# ETHERBEAR.net
KiCad netlist of a schematic drawn in EAGLE
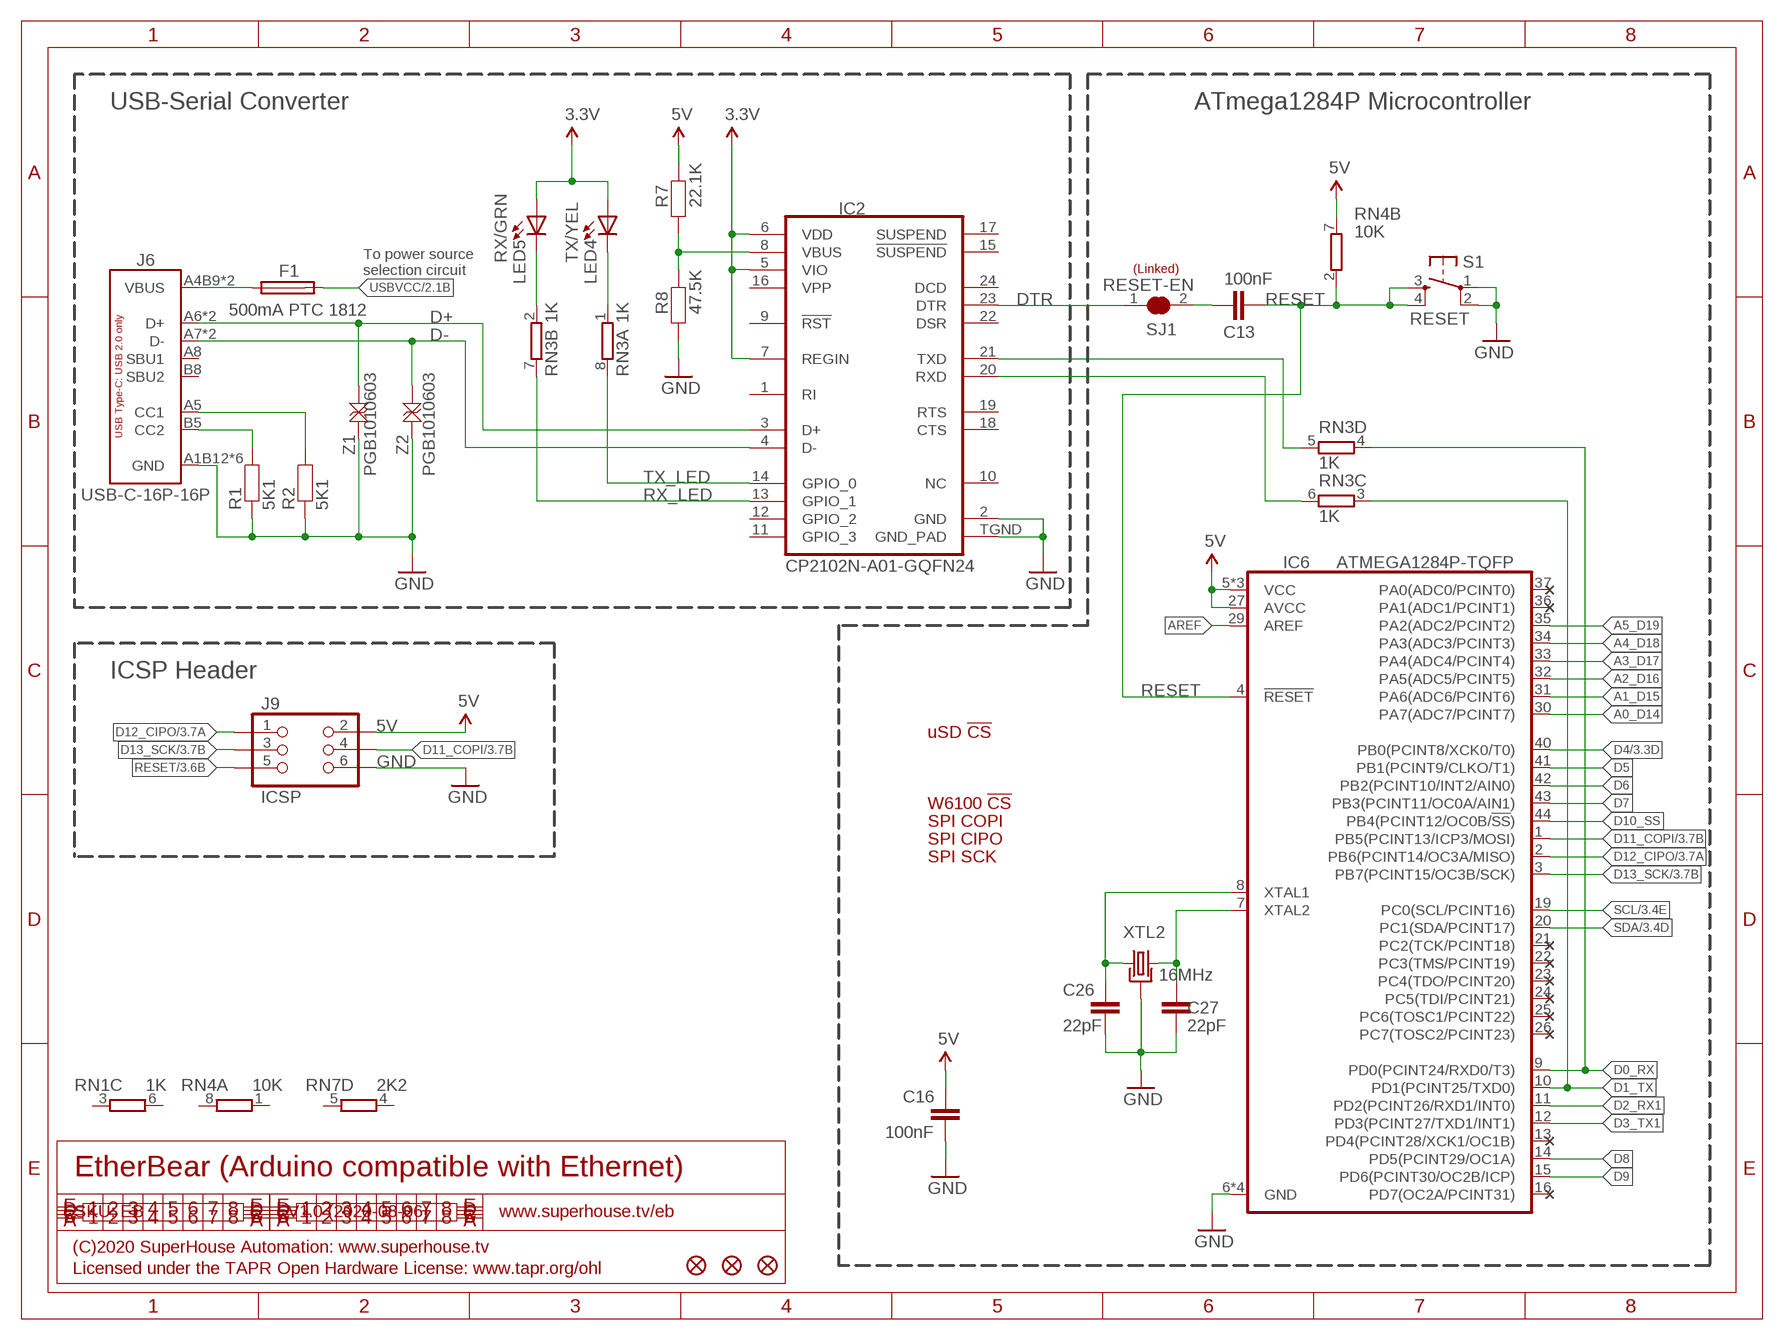
[diagram p0: schematic, sheet 1]
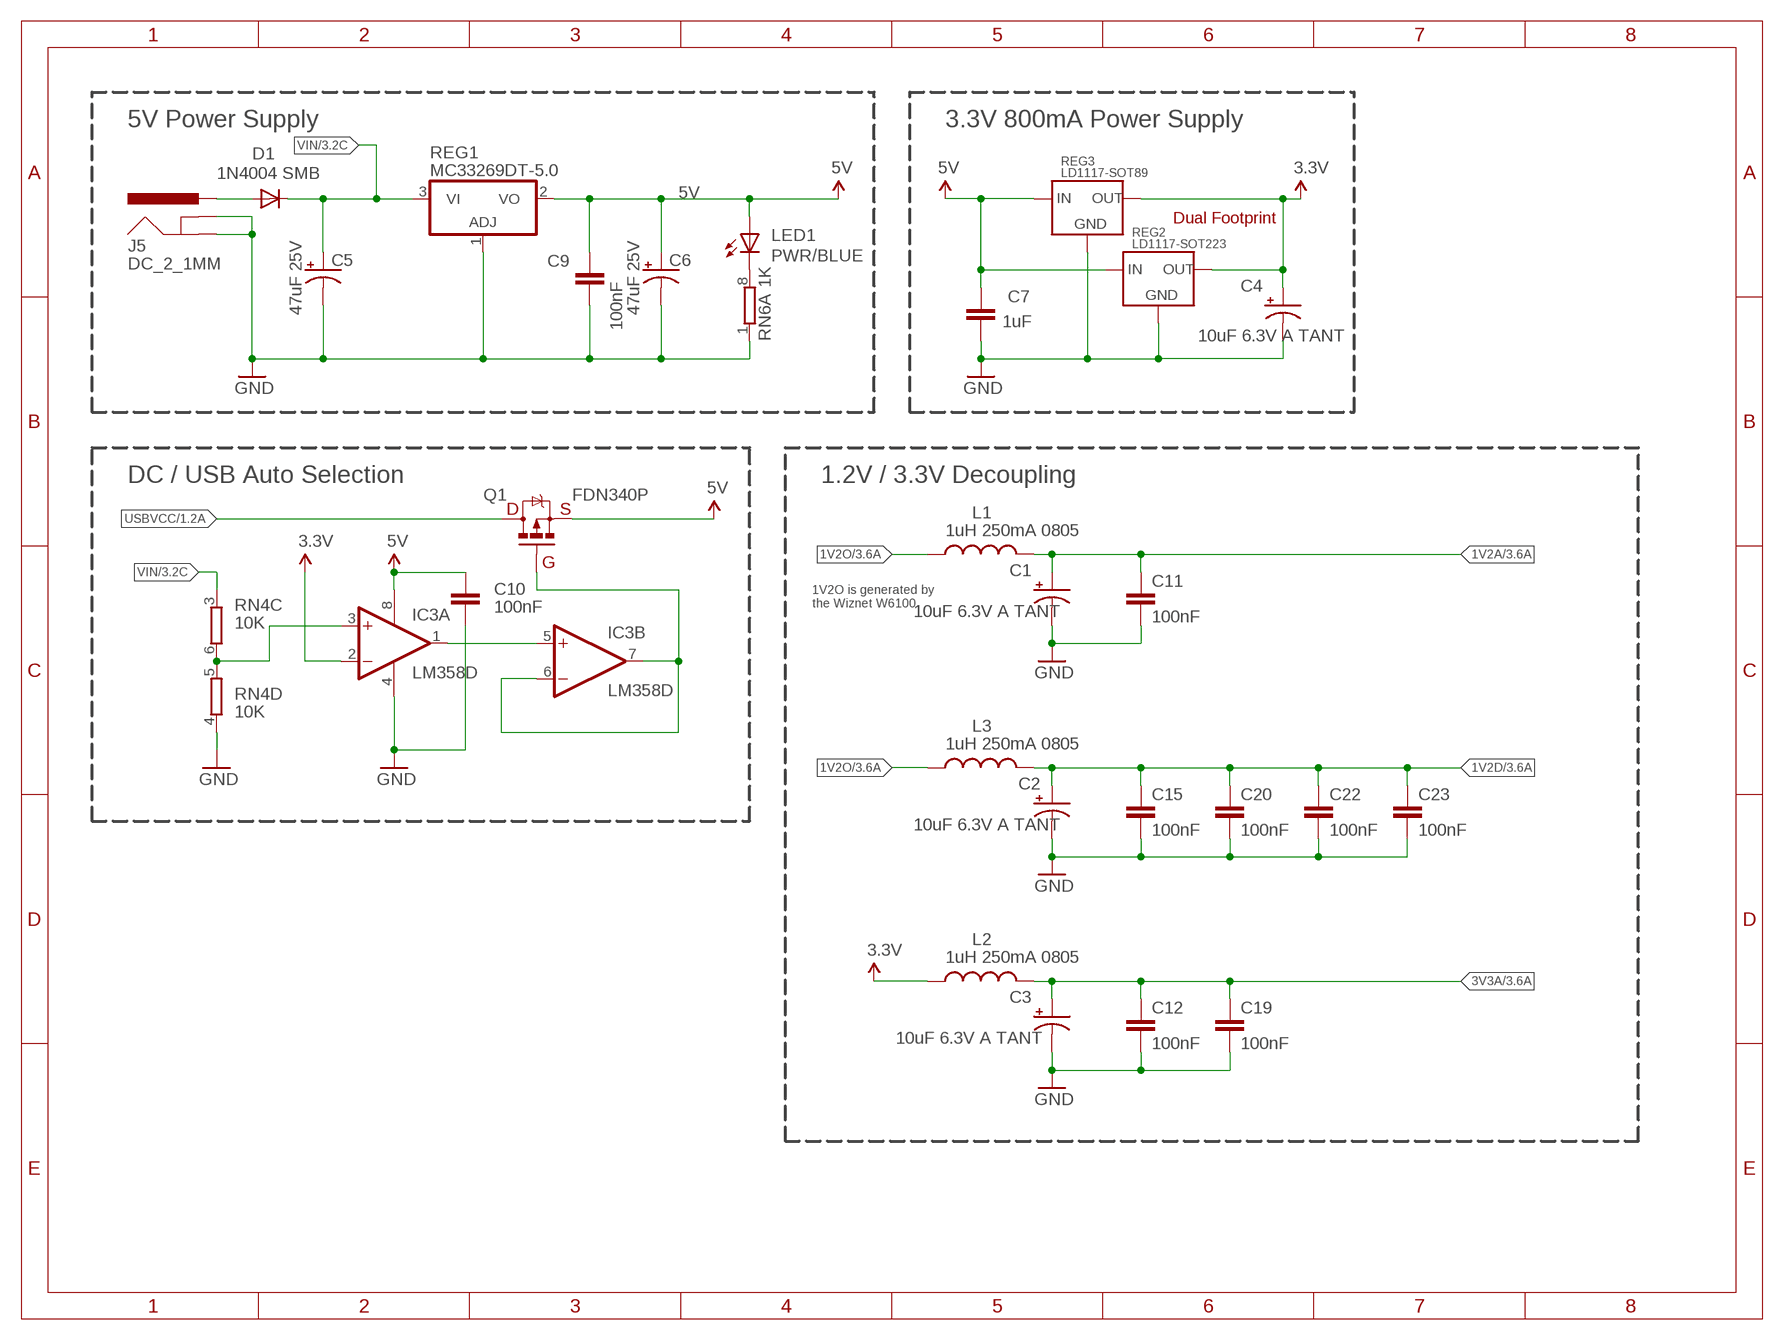
[diagram p1: schematic, sheet 2]
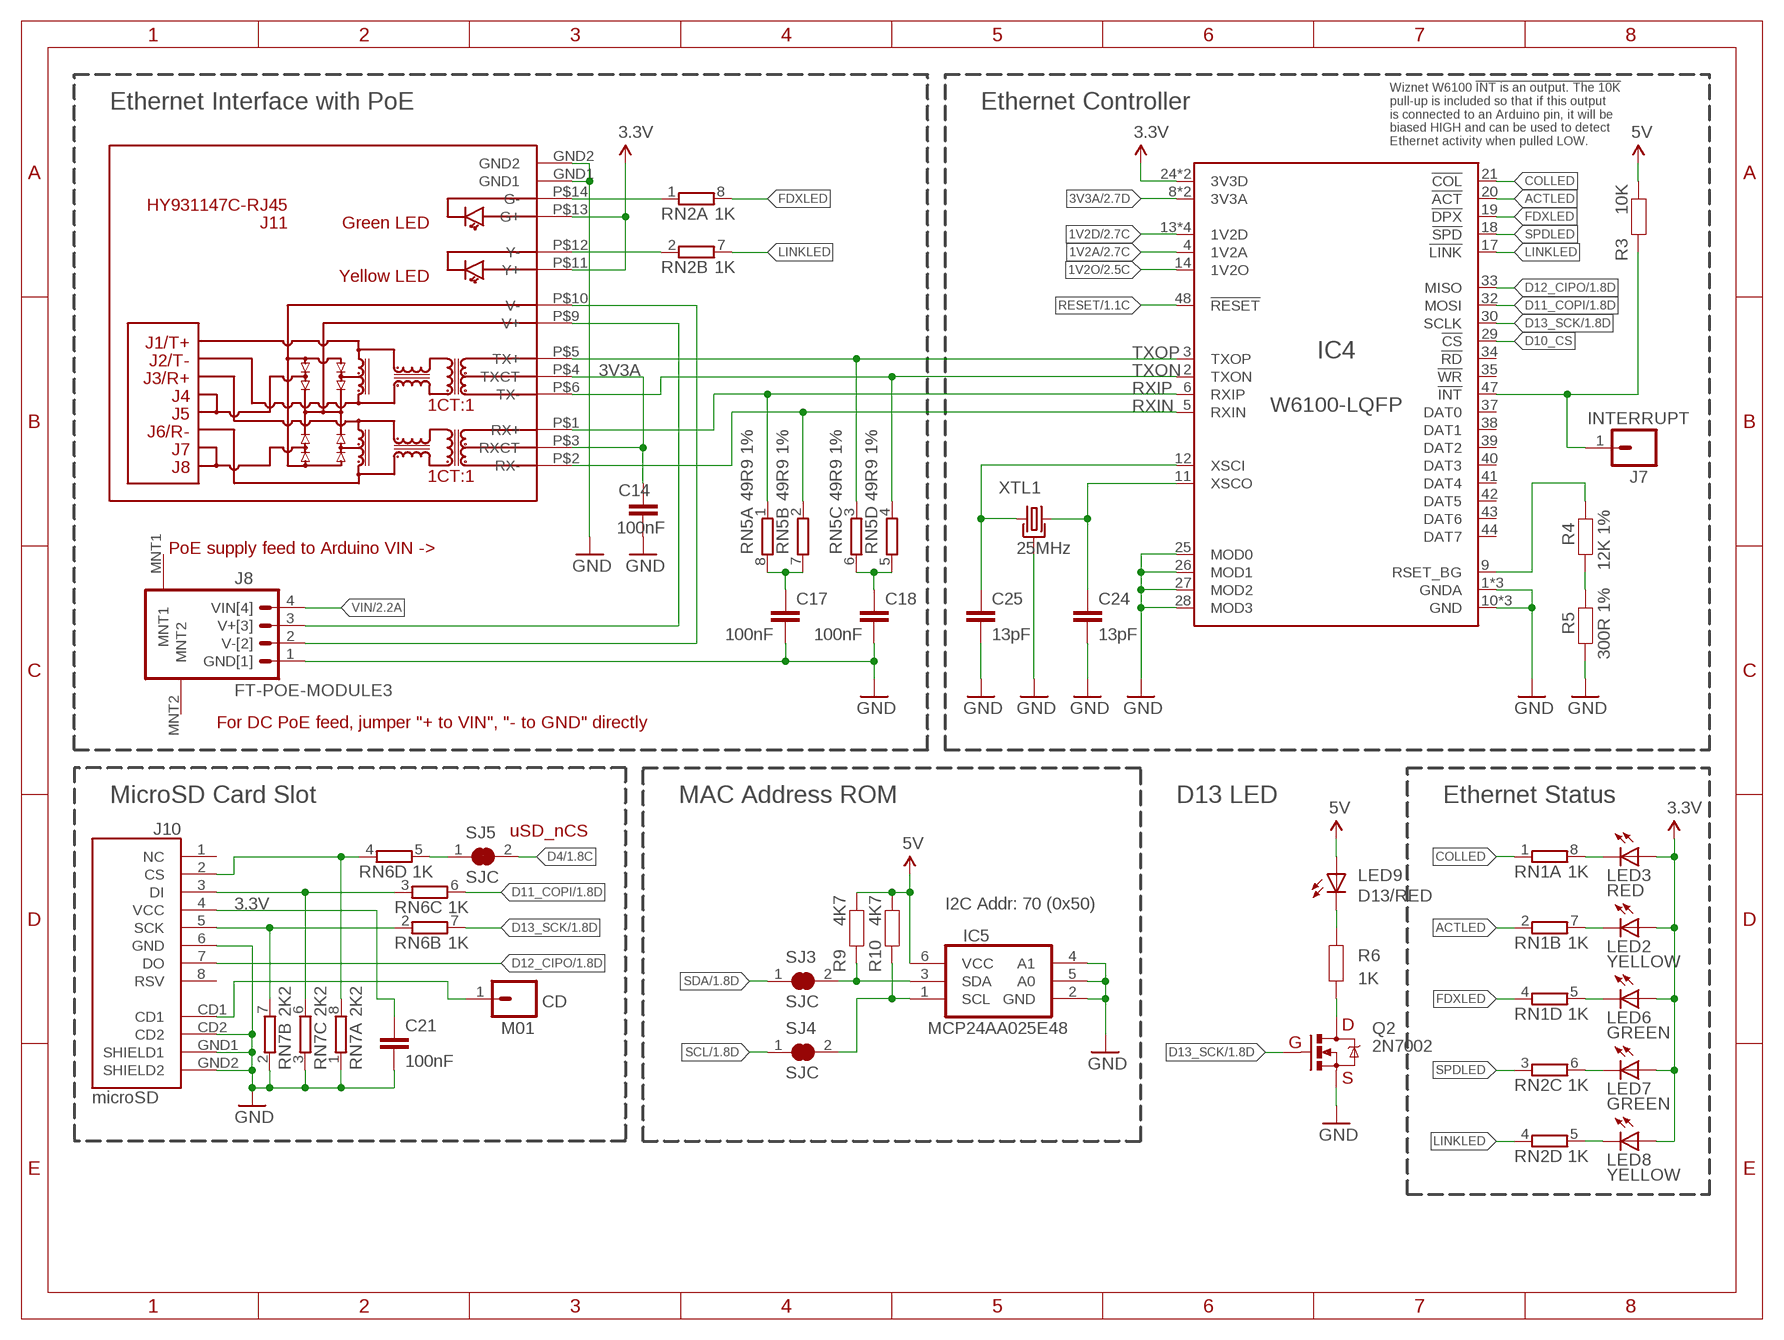
[diagram p2: schematic, sheet 3]
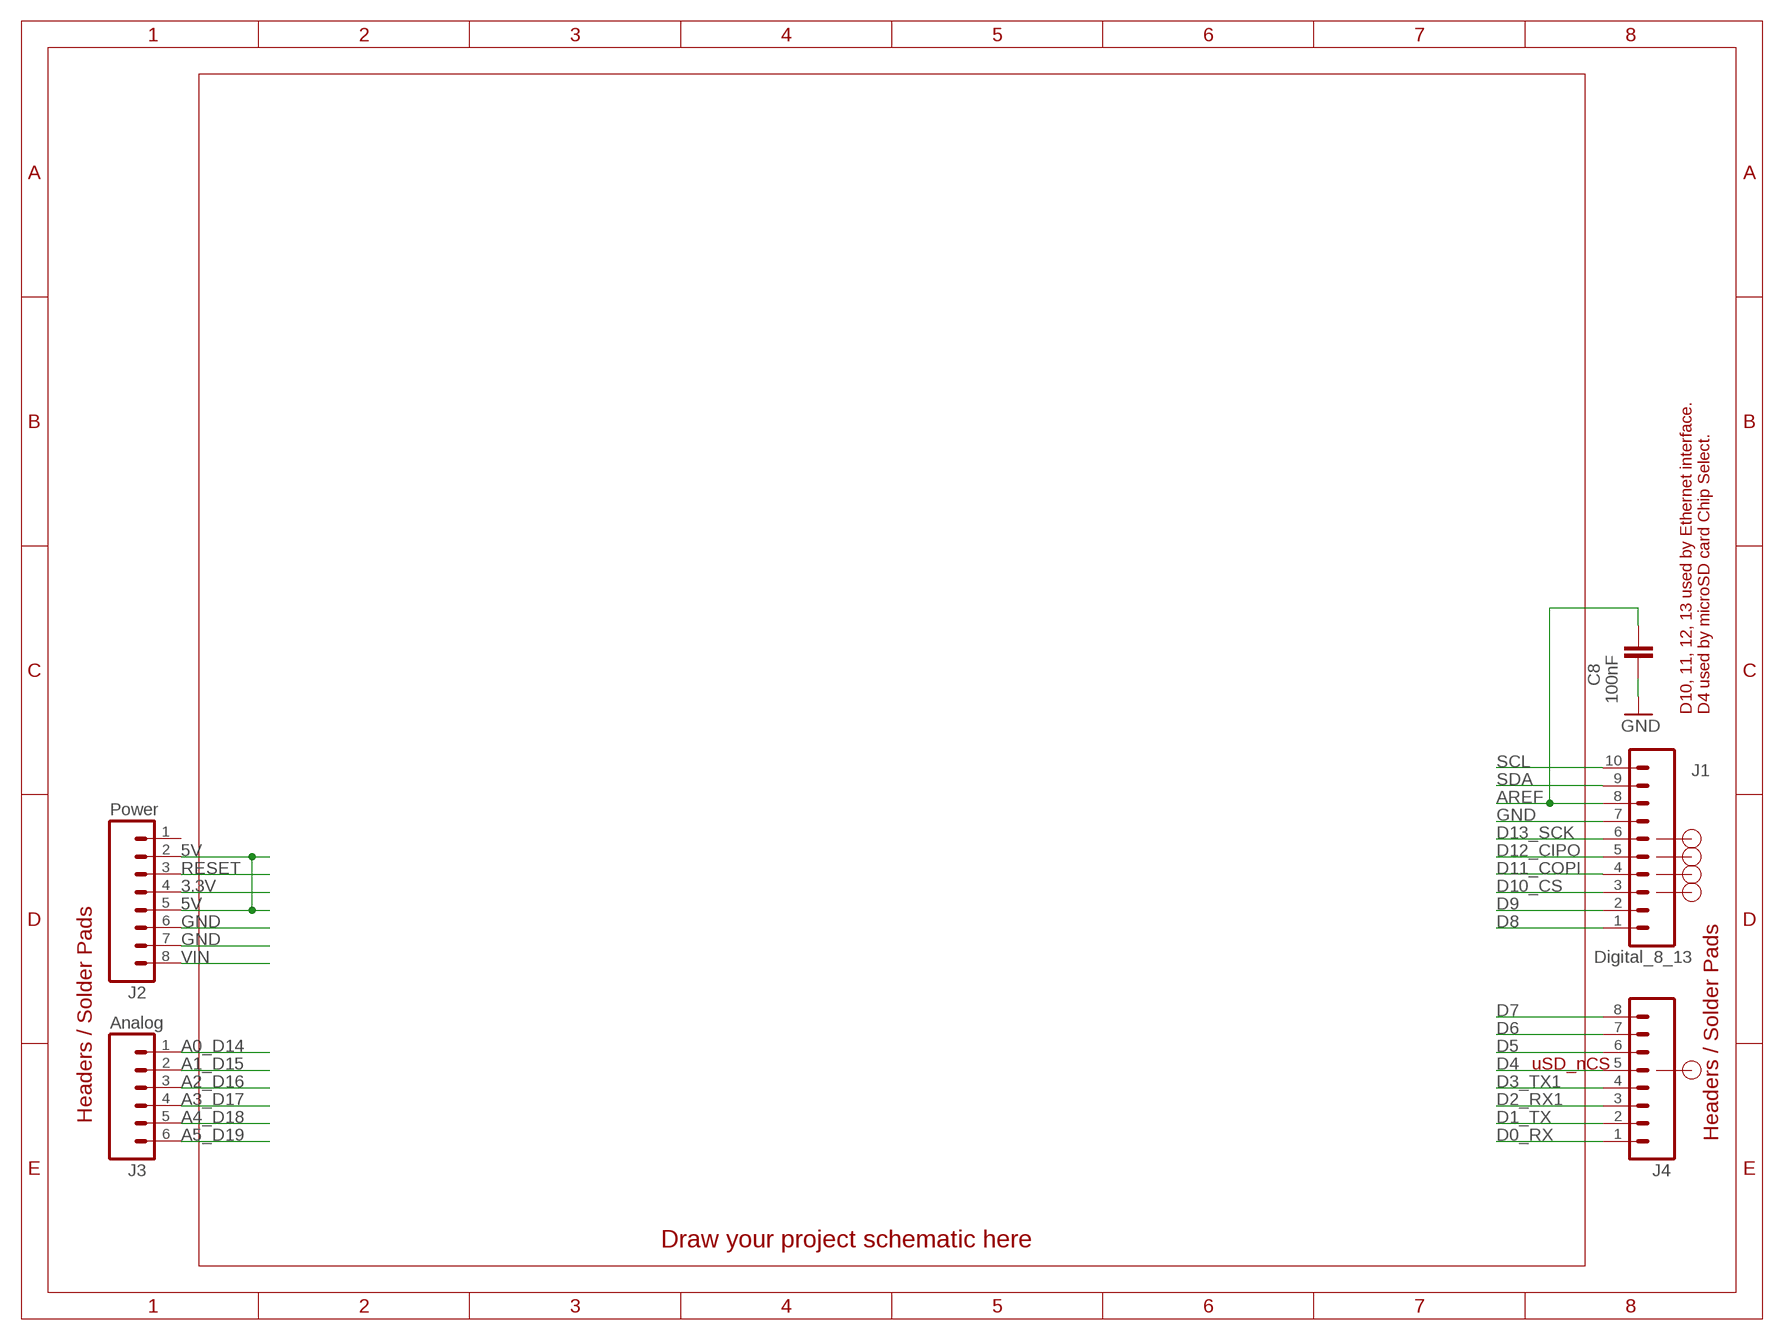
[diagram p3: schematic, sheet 4]

(export (version "E")
  (design (tool "Eeschema 10.0.6"))
  (components
    (comp (ref "C1")
      (value "10uF 6.3V A TANT")
      (footprint "eagle-import:EIA3216")
      (libsource (lib "eagle-import") (part "CAP_POL1206"))
    )
    (comp (ref "C2")
      (value "10uF 6.3V A TANT")
      (footprint "eagle-import:EIA3216")
      (libsource (lib "eagle-import") (part "CAP_POL1206"))
    )
    (comp (ref "C3")
      (value "10uF 6.3V A TANT")
      (footprint "eagle-import:EIA3216")
      (libsource (lib "eagle-import") (part "CAP_POL1206"))
    )
    (comp (ref "C4")
      (value "10uF 6.3V A TANT")
      (footprint "eagle-import:EIA3216")
      (libsource (lib "eagle-import") (part "CAP_POL1206"))
    )
    (comp (ref "C5")
      (value "47uF 25V")
      (footprint "eagle-import:PANASONIC_D")
      (libsource (lib "eagle-import") (part "CAP_POLD"))
    )
    (comp (ref "C6")
      (value "47uF 25V")
      (footprint "eagle-import:PANASONIC_D")
      (libsource (lib "eagle-import") (part "CAP_POLD"))
    )
    (comp (ref "C7")
      (value "1uF")
      (footprint "eagle-import:C0603")
      (libsource (lib "eagle-import") (part "CAP0603"))
    )
    (comp (ref "C9")
      (value "100nF")
      (footprint "eagle-import:C0603")
      (libsource (lib "eagle-import") (part "CAP0603"))
    )
    (comp (ref "C10")
      (value "100nF")
      (footprint "eagle-import:C0603")
      (libsource (lib "eagle-import") (part "CAP0603"))
    )
    (comp (ref "C11")
      (value "100nF")
      (footprint "eagle-import:C0603")
      (libsource (lib "eagle-import") (part "CAP0603"))
    )
    (comp (ref "C12")
      (value "100nF")
      (footprint "eagle-import:C0603")
      (libsource (lib "eagle-import") (part "CAP0603"))
    )
    (comp (ref "C15")
      (value "100nF")
      (footprint "eagle-import:C0603")
      (libsource (lib "eagle-import") (part "CAP0603"))
    )
    (comp (ref "C19")
      (value "100nF")
      (footprint "eagle-import:C0603")
      (libsource (lib "eagle-import") (part "CAP0603"))
    )
    (comp (ref "C20")
      (value "100nF")
      (footprint "eagle-import:C0603")
      (libsource (lib "eagle-import") (part "CAP0603"))
    )
    (comp (ref "C22")
      (value "100nF")
      (footprint "eagle-import:C0603")
      (libsource (lib "eagle-import") (part "CAP0603"))
    )
    (comp (ref "C23")
      (value "100nF")
      (footprint "eagle-import:C0603")
      (libsource (lib "eagle-import") (part "CAP0603"))
    )
    (comp (ref "D1")
      (value "1N4004 SMB")
      (footprint "eagle-import:SMA-DIODE")
      (libsource (lib "eagle-import") (part "DIODESMA"))
    )
    (comp (ref "IC3")
      (value "LM358D")
      (footprint "eagle-import:SO08")
      (libsource (lib "eagle-import") (part "LM358D"))
    )
    (comp (ref "J5")
      (value "DC_2_1MM")
      (footprint "eagle-import:POWER_JACK_SLOTS")
      (libsource (lib "eagle-import") (part "POWER_JACK-SLOTS"))
    )
    (comp (ref "L1")
      (value "1uH 250mA 0805")
      (footprint "eagle-import:0805-LARGE")
      (libsource (lib "eagle-import") (part "INDUCTOR0805-LARGE"))
    )
    (comp (ref "L2")
      (value "1uH 250mA 0805")
      (footprint "eagle-import:0805-LARGE")
      (libsource (lib "eagle-import") (part "INDUCTOR0805-LARGE"))
    )
    (comp (ref "L3")
      (value "1uH 250mA 0805")
      (footprint "eagle-import:0805-LARGE")
      (libsource (lib "eagle-import") (part "INDUCTOR0805-LARGE"))
    )
    (comp (ref "LED1")
      (value "PWR/BLUE")
      (footprint "eagle-import:LED-0603")
      (libsource (lib "eagle-import") (part "LED0603"))
    )
    (comp (ref "Q1")
      (value "FDN340P")
      (footprint "eagle-import:SOT23")
      (libsource (lib "eagle-import") (part "MOSFET-PCHANNEL"))
    )
    (comp (ref "REG1")
      (value "MC33269DT-5.0")
      (footprint "eagle-import:DPACK")
      (libsource (lib "eagle-import") (part "MC33269-X-D-5.0"))
    )
    (comp (ref "REG2")
      (value "LD1117-SOT223")
      (footprint "eagle-import:SOT-223")
      (libsource (lib "eagle-import") (part "LD1117-SOT223"))
    )
    (comp (ref "REG3")
      (value "LD1117-SOT89")
      (footprint "eagle-import:SOT89")
      (libsource (lib "eagle-import") (part "LD1117-SOT89"))
    )
    (comp (ref "RN4")
      (value "10K")
      (footprint "eagle-import:CAY16")
      (libsource (lib "eagle-import") (part "4R-NCAY16"))
    )
    (comp (ref "RN6")
      (value "1K")
      (footprint "eagle-import:CAY16")
      (libsource (lib "eagle-import") (part "4R-NCAY16"))
    )
    (comp (ref "C8")
      (value "100nF")
      (footprint "eagle-import:C0603")
      (libsource (lib "eagle-import") (part "CAP0603"))
    )
    (comp (ref "J1")
      (value "Digital_8_13")
      (footprint "eagle-import:1X10-S")
      (libsource (lib "eagle-import") (part "M10-SOCKET"))
    )
    (comp (ref "J2")
      (value "Power")
      (footprint "eagle-import:1X08-S")
      (libsource (lib "eagle-import") (part "M08-SOCKET"))
    )
    (comp (ref "J3")
      (value "Analog")
      (footprint "eagle-import:1X06-S")
      (libsource (lib "eagle-import") (part "M06-SOCKET"))
    )
    (comp (ref "J4")
      (value "Digital_0_7")
      (footprint "eagle-import:1X08-S")
      (libsource (lib "eagle-import") (part "M08-SOCKET"))
    )
    (comp (ref "C14")
      (value "100nF")
      (footprint "eagle-import:C0603")
      (libsource (lib "eagle-import") (part "CAP0603"))
    )
    (comp (ref "C17")
      (value "100nF")
      (footprint "eagle-import:C0603")
      (libsource (lib "eagle-import") (part "CAP0603"))
    )
    (comp (ref "C18")
      (value "100nF")
      (footprint "eagle-import:C0603")
      (libsource (lib "eagle-import") (part "CAP0603"))
    )
    (comp (ref "C21")
      (value "100nF")
      (footprint "eagle-import:C0603")
      (libsource (lib "eagle-import") (part "CAP0603"))
    )
    (comp (ref "C24")
      (value "13pF")
      (footprint "eagle-import:C0603")
      (libsource (lib "eagle-import") (part "CAP0603"))
    )
    (comp (ref "C25")
      (value "13pF")
      (footprint "eagle-import:C0603")
      (libsource (lib "eagle-import") (part "CAP0603"))
    )
    (comp (ref "CD")
      (value "M01")
      (footprint "eagle-import:1X01")
      (libsource (lib "eagle-import") (part "M01-PLAIN"))
    )
    (comp (ref "IC4")
      (value "W6100-LQFP")
      (footprint "eagle-import:LQFP48")
      (libsource (lib "eagle-import") (part "W6100-LQFP"))
    )
    (comp (ref "IC5")
      (value "MCP24AA025E48")
      (footprint "eagle-import:SOT23-6")
      (libsource (lib "eagle-import") (part "MCP24AA025E48"))
    )
    (comp (ref "J7")
      (value "INTERRUPT")
      (footprint "eagle-import:1X01")
      (libsource (lib "eagle-import") (part "M01-PLAIN"))
    )
    (comp (ref "J8")
      (value "FT-POE-MODULE3")
      (footprint "eagle-import:FT-POE-MODULE-NOLABEL")
      (libsource (lib "eagle-import") (part "FT-POE-MODULE3"))
    )
    (comp (ref "J10")
      (value "microSD")
      (footprint "eagle-import:MICRO-SD-SOCKET-PP")
      (libsource (lib "eagle-import") (part "USD-SOCKETNEW"))
    )
    (comp (ref "J11")
      (value "HY931147C-RJ45")
      (footprint "eagle-import:HY931147C")
      (libsource (lib "eagle-import") (part "HY931147C-RJ45"))
    )
    (comp (ref "LED2")
      (value "YELLOW")
      (footprint "eagle-import:LED-0603")
      (libsource (lib "eagle-import") (part "LED0603"))
    )
    (comp (ref "LED3")
      (value "RED")
      (footprint "eagle-import:LED-0603")
      (libsource (lib "eagle-import") (part "LED0603"))
    )
    (comp (ref "LED6")
      (value "GREEN")
      (footprint "eagle-import:LED-0603")
      (libsource (lib "eagle-import") (part "LED0603"))
    )
    (comp (ref "LED7")
      (value "GREEN")
      (footprint "eagle-import:LED-0603")
      (libsource (lib "eagle-import") (part "LED0603"))
    )
    (comp (ref "LED8")
      (value "YELLOW")
      (footprint "eagle-import:LED-0603")
      (libsource (lib "eagle-import") (part "LED0603"))
    )
    (comp (ref "LED9")
      (value "D13/RED")
      (footprint "eagle-import:LED-0603")
      (libsource (lib "eagle-import") (part "LED0603"))
    )
    (comp (ref "Q2")
      (value "2N7002")
      (footprint "eagle-import:SOT23-3")
      (libsource (lib "eagle-import") (part "MOSFET-NCHANNEL-233"))
    )
    (comp (ref "R3")
      (value "10K")
      (footprint "eagle-import:R0603")
      (libsource (lib "eagle-import") (part "RESISTOR0603"))
    )
    (comp (ref "R4")
      (value "12K 1%")
      (footprint "eagle-import:R0603")
      (libsource (lib "eagle-import") (part "RESISTOR0603"))
    )
    (comp (ref "R5")
      (value "300R 1%")
      (footprint "eagle-import:R0603")
      (libsource (lib "eagle-import") (part "RESISTOR0603"))
    )
    (comp (ref "R6")
      (value "1K")
      (footprint "eagle-import:R0603")
      (libsource (lib "eagle-import") (part "RESISTOR0603"))
    )
    (comp (ref "R9")
      (value "4K7")
      (footprint "eagle-import:R0603")
      (libsource (lib "eagle-import") (part "RESISTOR0603"))
    )
    (comp (ref "R10")
      (value "4K7")
      (footprint "eagle-import:R0603")
      (libsource (lib "eagle-import") (part "RESISTOR0603"))
    )
    (comp (ref "RN1")
      (value "1K")
      (footprint "eagle-import:CAY16")
      (libsource (lib "eagle-import") (part "4R-NCAY16"))
    )
    (comp (ref "RN2")
      (value "1K")
      (footprint "eagle-import:CAY16")
      (libsource (lib "eagle-import") (part "4R-NCAY16"))
    )
    (comp (ref "RN5")
      (value "49R9 1%")
      (footprint "eagle-import:CAY16")
      (libsource (lib "eagle-import") (part "4R-NCAY16"))
    )
    (comp (ref "RN7")
      (value "2K2")
      (footprint "eagle-import:CAY16")
      (libsource (lib "eagle-import") (part "4R-NCAY16"))
    )
    (comp (ref "SJ3")
      (value "SJC")
      (footprint "eagle-import:SJC")
      (libsource (lib "eagle-import") (part "SJC-NORMAL"))
    )
    (comp (ref "SJ4")
      (value "SJC")
      (footprint "eagle-import:SJC")
      (libsource (lib "eagle-import") (part "SJC-NORMAL"))
    )
    (comp (ref "SJ5")
      (value "SJC")
      (footprint "eagle-import:SJC")
      (libsource (lib "eagle-import") (part "SJC-NORMAL"))
    )
    (comp (ref "XTL1")
      (value "25MHz")
      (footprint "eagle-import:CRYSTAL-SMD-3X2")
      (libsource (lib "eagle-import") (part "CRYSTAL-GND3X2"))
    )
    (comp (ref "C13")
      (value "100nF")
      (footprint "eagle-import:C0603")
      (libsource (lib "eagle-import") (part "CAP0603"))
    )
    (comp (ref "C16")
      (value "100nF")
      (footprint "eagle-import:C0603")
      (libsource (lib "eagle-import") (part "CAP0603"))
    )
    (comp (ref "C26")
      (value "22pF")
      (footprint "eagle-import:C0603")
      (libsource (lib "eagle-import") (part "CAP0603"))
    )
    (comp (ref "C27")
      (value "22pF")
      (footprint "eagle-import:C0603")
      (libsource (lib "eagle-import") (part "CAP0603"))
    )
    (comp (ref "F1")
      (value "500mA PTC 1812")
      (footprint "eagle-import:1812")
      (libsource (lib "eagle-import") (part "PTC050"))
    )
    (comp (ref "FID1")
      (value "FIDUCIAL1X2.5")
      (footprint "eagle-import:FIDUCIAL-1X2.5")
      (libsource (lib "eagle-import") (part "FIDUCIAL1X2.5"))
    )
    (comp (ref "FID2")
      (value "FIDUCIAL1X2.5")
      (footprint "eagle-import:FIDUCIAL-1X2.5")
      (libsource (lib "eagle-import") (part "FIDUCIAL1X2.5"))
    )
    (comp (ref "FID3")
      (value "FIDUCIAL1X2.5")
      (footprint "eagle-import:FIDUCIAL-1X2.5")
      (libsource (lib "eagle-import") (part "FIDUCIAL1X2.5"))
    )
    (comp (ref "IC2")
      (value "CP2102N-A01-GQFN24")
      (footprint "eagle-import:QFN-24")
      (libsource (lib "eagle-import") (part "CP2104"))
    )
    (comp (ref "IC6")
      (value "ATMEGA1284P-TQFP")
      (footprint "eagle-import:TQFP44")
      (libsource (lib "eagle-import") (part "ATMEGA1284P-TQFP"))
    )
    (comp (ref "J6")
      (value "USB-C-16P-16P")
      (footprint "eagle-import:USB-C-16P")
      (libsource (lib "eagle-import") (part "USB-C-16P-16P"))
    )
    (comp (ref "J9")
      (value "ICSP")
      (footprint "eagle-import:2X03-ICSP")
      (libsource (lib "eagle-import") (part "ICSP-PIN"))
    )
    (comp (ref "LED4")
      (value "TX/YEL")
      (footprint "eagle-import:LED-0603")
      (libsource (lib "eagle-import") (part "LED0603"))
    )
    (comp (ref "LED5")
      (value "RX/GRN")
      (footprint "eagle-import:LED-0603")
      (libsource (lib "eagle-import") (part "LED0603"))
    )
    (comp (ref "R1")
      (value "5K1")
      (footprint "eagle-import:R0603")
      (libsource (lib "eagle-import") (part "RESISTOR0603"))
    )
    (comp (ref "R2")
      (value "5K1")
      (footprint "eagle-import:R0603")
      (libsource (lib "eagle-import") (part "RESISTOR0603"))
    )
    (comp (ref "R7")
      (value "22.1K")
      (footprint "eagle-import:R0603")
      (libsource (lib "eagle-import") (part "RESISTOR0603"))
    )
    (comp (ref "R8")
      (value "47.5K")
      (footprint "eagle-import:R0603")
      (libsource (lib "eagle-import") (part "RESISTOR0603"))
    )
    (comp (ref "RN3")
      (value "1K")
      (footprint "eagle-import:CAY16")
      (libsource (lib "eagle-import") (part "4R-NCAY16"))
    )
    (comp (ref "S1")
      (value "RESET")
      (footprint "eagle-import:TACTILE_SMT-6MM")
      (libsource (lib "eagle-import") (part "TAC_SWITCH-SMT-6"))
    )
    (comp (ref "SJ1")
      (value "RESET-EN")
      (footprint "eagle-import:SJC")
      (libsource (lib "eagle-import") (part "SJC-NORMAL"))
    )
    (comp (ref "XTL2")
      (value "16MHz")
      (footprint "eagle-import:CRYSTAL-SMD-3X2")
      (libsource (lib "eagle-import") (part "CRYSTAL-GND3X2"))
    )
    (comp (ref "Z1")
      (value "PGB1010603")
      (footprint "eagle-import:TVS0603")
      (libsource (lib "eagle-import") (part "TVS0603"))
    )
    (comp (ref "Z2")
      (value "PGB1010603")
      (footprint "eagle-import:TVS0603")
      (libsource (lib "eagle-import") (part "TVS0603"))
    )
  )
  (nets
    (net (code "1") (name "1V2A") (class "Default")
      (node (ref "C1") (pin "A") (pinfunction "+_A") (pintype "passive"))
      (node (ref "C11") (pin "1") (pinfunction "1_1") (pintype "passive"))
      (node (ref "IC4") (pin "4") (pinfunction "1V2A_4") (pintype "bidirectional"))
      (node (ref "L1") (pin "2") (pinfunction "2_2") (pintype "passive"))
    )
    (net (code "2") (name "1V2D") (class "Default")
      (node (ref "C15") (pin "1") (pinfunction "1_1") (pintype "passive"))
      (node (ref "C2") (pin "A") (pinfunction "+_A") (pintype "passive"))
      (node (ref "C20") (pin "1") (pinfunction "1_1") (pintype "passive"))
      (node (ref "C22") (pin "1") (pinfunction "1_1") (pintype "passive"))
      (node (ref "C23") (pin "1") (pinfunction "1_1") (pintype "passive"))
      (node (ref "IC4") (pin "13") (pinfunction "1V2D_13") (pintype "bidirectional"))
      (node (ref "IC4") (pin "22") (pinfunction "1V2D_22") (pintype "bidirectional"))
      (node (ref "IC4") (pin "31") (pinfunction "1V2D_31") (pintype "bidirectional"))
      (node (ref "IC4") (pin "45") (pinfunction "1V2D_45") (pintype "bidirectional"))
      (node (ref "L3") (pin "2") (pinfunction "2_2") (pintype "passive"))
    )
    (net (code "3") (name "1V2O") (class "Default")
      (node (ref "IC4") (pin "14") (pinfunction "1V2O_14") (pintype "bidirectional"))
      (node (ref "L1") (pin "1") (pinfunction "1_1") (pintype "passive"))
      (node (ref "L3") (pin "1") (pinfunction "1_1") (pintype "passive"))
    )
    (net (code "4") (name "3.3V") (class "Default")
      (node (ref "C21") (pin "1") (pinfunction "1_1") (pintype "passive"))
      (node (ref "C4") (pin "A") (pinfunction "+_A") (pintype "passive"))
      (node (ref "IC2") (pin "5") (pinfunction "VIO_5") (pintype "bidirectional"))
      (node (ref "IC2") (pin "6") (pinfunction "VDD_6") (pintype "power_in"))
      (node (ref "IC2") (pin "7") (pinfunction "REGIN_7") (pintype "power_in"))
      (node (ref "IC3") (pin "2") (pinfunction "-IN_2") (pintype "input"))
      (node (ref "IC4") (pin "24") (pinfunction "3V3D_24") (pintype "bidirectional"))
      (node (ref "IC4") (pin "36") (pinfunction "3V3D_36") (pintype "bidirectional"))
      (node (ref "J10") (pin "4") (pinfunction "VCC_4") (pintype "bidirectional"))
      (node (ref "J11") (pin "P$11") (pinfunction "Y+_P$11") (pintype "bidirectional"))
      (node (ref "J11") (pin "P$13") (pinfunction "G+_P$13") (pintype "bidirectional"))
      (node (ref "J2") (pin "4") (pinfunction "4_4") (pintype "passive"))
      (node (ref "L2") (pin "1") (pinfunction "1_1") (pintype "passive"))
      (node (ref "LED2") (pin "A") (pinfunction "A_A") (pintype "passive"))
      (node (ref "LED3") (pin "A") (pinfunction "A_A") (pintype "passive"))
      (node (ref "LED4") (pin "A") (pinfunction "A_A") (pintype "passive"))
      (node (ref "LED5") (pin "A") (pinfunction "A_A") (pintype "passive"))
      (node (ref "LED6") (pin "A") (pinfunction "A_A") (pintype "passive"))
      (node (ref "LED7") (pin "A") (pinfunction "A_A") (pintype "passive"))
      (node (ref "LED8") (pin "A") (pinfunction "A_A") (pintype "passive"))
      (node (ref "REG2") (pin "2") (pinfunction "OUT_2") (pintype "power_in"))
      (node (ref "REG2") (pin "4") (pinfunction "OUT_4") (pintype "power_in"))
      (node (ref "REG3") (pin "2") (pinfunction "OUT_2") (pintype "power_in"))
      (node (ref "REG3") (pin "4") (pinfunction "OUT_4") (pintype "power_in"))
    )
    (net (code "5") (name "3V3A") (class "Default")
      (node (ref "C12") (pin "1") (pinfunction "1_1") (pintype "passive"))
      (node (ref "C14") (pin "1") (pinfunction "1_1") (pintype "passive"))
      (node (ref "C19") (pin "1") (pinfunction "1_1") (pintype "passive"))
      (node (ref "C3") (pin "A") (pinfunction "+_A") (pintype "passive"))
      (node (ref "IC4") (pin "15") (pinfunction "3V3A_15") (pintype "bidirectional"))
      (node (ref "IC4") (pin "8") (pinfunction "3V3A_8") (pintype "bidirectional"))
      (node (ref "J11") (pin "P$3") (pinfunction "RXCT_P$3") (pintype "bidirectional"))
      (node (ref "J11") (pin "P$4") (pinfunction "TXCT_P$4") (pintype "bidirectional"))
      (node (ref "L2") (pin "2") (pinfunction "2_2") (pintype "passive"))
    )
    (net (code "6") (name "5V") (class "Default")
      (node (ref "C10") (pin "1") (pinfunction "1_1") (pintype "passive"))
      (node (ref "C16") (pin "1") (pinfunction "1_1") (pintype "passive"))
      (node (ref "C6") (pin "+") (pinfunction "+_+") (pintype "passive"))
      (node (ref "C7") (pin "1") (pinfunction "1_1") (pintype "passive"))
      (node (ref "C9") (pin "1") (pinfunction "1_1") (pintype "passive"))
      (node (ref "IC3") (pin "8") (pinfunction "V+_8") (pintype "power_in"))
      (node (ref "IC5") (pin "6") (pinfunction "VCC_6") (pintype "power_in"))
      (node (ref "IC6") (pin "17") (pinfunction "VCC_17") (pintype "bidirectional"))
      (node (ref "IC6") (pin "27") (pinfunction "AVCC_27") (pintype "bidirectional"))
      (node (ref "IC6") (pin "28") (pinfunction "VCC_28") (pintype "bidirectional"))
      (node (ref "IC6") (pin "5") (pinfunction "VCC_5") (pintype "bidirectional"))
      (node (ref "J2") (pin "2") (pinfunction "2_2") (pintype "passive"))
      (node (ref "J2") (pin "5") (pinfunction "5_5") (pintype "passive"))
      (node (ref "J9") (pin "2") (pinfunction "2_2") (pintype "passive"))
      (node (ref "LED1") (pin "A") (pinfunction "A_A") (pintype "passive"))
      (node (ref "LED9") (pin "A") (pinfunction "A_A") (pintype "passive"))
      (node (ref "Q1") (pin "2") (pinfunction "S_2") (pintype "passive"))
      (node (ref "R10") (pin "1") (pinfunction "1_1") (pintype "passive"))
      (node (ref "R3") (pin "1") (pinfunction "1_1") (pintype "passive"))
      (node (ref "R7") (pin "2") (pinfunction "2_2") (pintype "passive"))
      (node (ref "R9") (pin "1") (pinfunction "1_1") (pintype "passive"))
      (node (ref "REG1") (pin "2") (pinfunction "VO_2") (pintype "passive"))
      (node (ref "REG2") (pin "3") (pinfunction "IN_3") (pintype "input"))
      (node (ref "REG3") (pin "3") (pinfunction "IN_3") (pintype "input"))
      (node (ref "RN4") (pin "7") (pinfunction "2_7") (pintype "passive"))
    )
    (net (code "7") (name "A0_D14") (class "Default")
      (node (ref "IC6") (pin "30") (pinfunction "PA7(ADC7/PCINT7)_30") (pintype "bidirectional"))
      (node (ref "J3") (pin "1") (pinfunction "1_1") (pintype "passive"))
    )
    (net (code "8") (name "A1_D15") (class "Default")
      (node (ref "IC6") (pin "31") (pinfunction "PA6(ADC6/PCINT6)_31") (pintype "bidirectional"))
      (node (ref "J3") (pin "2") (pinfunction "2_2") (pintype "passive"))
    )
    (net (code "9") (name "A2_D16") (class "Default")
      (node (ref "IC6") (pin "32") (pinfunction "PA5(ADC5/PCINT5)_32") (pintype "bidirectional"))
      (node (ref "J3") (pin "3") (pinfunction "3_3") (pintype "passive"))
    )
    (net (code "10") (name "A3_D17") (class "Default")
      (node (ref "IC6") (pin "33") (pinfunction "PA4(ADC4/PCINT4)_33") (pintype "bidirectional"))
      (node (ref "J3") (pin "4") (pinfunction "4_4") (pintype "passive"))
    )
    (net (code "11") (name "A4_D18") (class "Default")
      (node (ref "IC6") (pin "34") (pinfunction "PA3(ADC3/PCINT3)_34") (pintype "bidirectional"))
      (node (ref "J3") (pin "5") (pinfunction "5_5") (pintype "passive"))
    )
    (net (code "12") (name "A5_D19") (class "Default")
      (node (ref "IC6") (pin "35") (pinfunction "PA2(ADC2/PCINT2)_35") (pintype "bidirectional"))
      (node (ref "J3") (pin "6") (pinfunction "6_6") (pintype "passive"))
    )
    (net (code "13") (name "ACTLED") (class "Default")
      (node (ref "IC4") (pin "20") (pinfunction "~{ACT}_20") (pintype "bidirectional"))
      (node (ref "RN1") (pin "2") (pinfunction "1_2") (pintype "passive"))
    )
    (net (code "14") (name "AREF") (class "Default")
      (node (ref "C8") (pin "1") (pinfunction "1_1") (pintype "passive"))
      (node (ref "IC6") (pin "29") (pinfunction "AREF_29") (pintype "bidirectional"))
      (node (ref "J1") (pin "8") (pinfunction "8_8") (pintype "passive"))
    )
    (net (code "15") (name "COLLED") (class "Default")
      (node (ref "IC4") (pin "21") (pinfunction "~{COL}_21") (pintype "bidirectional"))
      (node (ref "RN1") (pin "1") (pinfunction "1_1") (pintype "passive"))
    )
    (net (code "16") (name "D+") (class "Default")
      (node (ref "IC2") (pin "3") (pinfunction "D+_3") (pintype "bidirectional"))
      (node (ref "J6") (pin "A6") (pinfunction "D+_A6") (pintype "bidirectional"))
      (node (ref "J6") (pin "B6") (pinfunction "D+_B6") (pintype "bidirectional"))
      (node (ref "Z1") (pin "1") (pinfunction "1_1") (pintype "passive"))
    )
    (net (code "17") (name "D-") (class "Default")
      (node (ref "IC2") (pin "4") (pinfunction "D-_4") (pintype "bidirectional"))
      (node (ref "J6") (pin "A7") (pinfunction "D-_A7") (pintype "bidirectional"))
      (node (ref "J6") (pin "B7") (pinfunction "D-_B7") (pintype "bidirectional"))
      (node (ref "Z2") (pin "1") (pinfunction "1_1") (pintype "passive"))
    )
    (net (code "18") (name "D0_RX") (class "Default")
      (node (ref "IC6") (pin "9") (pinfunction "PD0(PCINT24/RXD0/T3)_9") (pintype "bidirectional"))
      (node (ref "J4") (pin "1") (pinfunction "1_1") (pintype "passive"))
      (node (ref "RN3") (pin "4") (pinfunction "1_4") (pintype "passive"))
    )
    (net (code "19") (name "D1_TX") (class "Default")
      (node (ref "IC6") (pin "10") (pinfunction "PD1(PCINT25/TXD0)_10") (pintype "bidirectional"))
      (node (ref "J4") (pin "2") (pinfunction "2_2") (pintype "passive"))
      (node (ref "RN3") (pin "3") (pinfunction "1_3") (pintype "passive"))
    )
    (net (code "20") (name "D2_RX1") (class "Default")
      (node (ref "IC6") (pin "11") (pinfunction "PD2(PCINT26/RXD1/INT0)_11") (pintype "bidirectional"))
      (node (ref "J4") (pin "3") (pinfunction "3_3") (pintype "passive"))
    )
    (net (code "21") (name "D3_TX1") (class "Default")
      (node (ref "IC6") (pin "12") (pinfunction "PD3(PCINT27/TXD1/INT1)_12") (pintype "bidirectional"))
      (node (ref "J4") (pin "4") (pinfunction "4_4") (pintype "passive"))
    )
    (net (code "22") (name "D4") (class "Default")
      (node (ref "IC6") (pin "40") (pinfunction "PB0(PCINT8/XCK0/T0)_40") (pintype "bidirectional"))
      (node (ref "J4") (pin "5") (pinfunction "5_5") (pintype "passive"))
      (node (ref "SJ5") (pin "2") (pinfunction "2_2") (pintype "passive"))
    )
    (net (code "23") (name "D5") (class "Default")
      (node (ref "IC6") (pin "41") (pinfunction "PB1(PCINT9/CLKO/T1)_41") (pintype "bidirectional"))
      (node (ref "J4") (pin "6") (pinfunction "6_6") (pintype "passive"))
    )
    (net (code "24") (name "D6") (class "Default")
      (node (ref "IC6") (pin "42") (pinfunction "PB2(PCINT10/INT2/AIN0)_42") (pintype "bidirectional"))
      (node (ref "J4") (pin "7") (pinfunction "7_7") (pintype "passive"))
    )
    (net (code "25") (name "D7") (class "Default")
      (node (ref "IC6") (pin "43") (pinfunction "PB3(PCINT11/OC0A/AIN1)_43") (pintype "bidirectional"))
      (node (ref "J4") (pin "8") (pinfunction "8_8") (pintype "passive"))
    )
    (net (code "26") (name "D8") (class "Default")
      (node (ref "IC6") (pin "14") (pinfunction "PD5(PCINT29/OC1A)_14") (pintype "bidirectional"))
      (node (ref "J1") (pin "1") (pinfunction "1_1") (pintype "passive"))
    )
    (net (code "27") (name "D9") (class "Default")
      (node (ref "IC6") (pin "15") (pinfunction "PD6(PCINT30/OC2B/ICP)_15") (pintype "bidirectional"))
      (node (ref "J1") (pin "2") (pinfunction "2_2") (pintype "passive"))
    )
    (net (code "28") (name "D10_CS") (class "Default")
      (node (ref "IC4") (pin "29") (pinfunction "~{CS}_29") (pintype "bidirectional"))
      (node (ref "J1") (pin "3") (pinfunction "3_3") (pintype "passive"))
    )
    (net (code "29") (name "D10_SS") (class "Default")
      (node (ref "IC6") (pin "44") (pinfunction "PB4(PCINT12/OC0B/~{SS})_44") (pintype "bidirectional"))
    )
    (net (code "30") (name "D11_COPI") (class "Default")
      (node (ref "IC4") (pin "32") (pinfunction "MOSI_32") (pintype "bidirectional"))
      (node (ref "IC6") (pin "1") (pinfunction "PB5(PCINT13/ICP3/MOSI)_1") (pintype "bidirectional"))
      (node (ref "J1") (pin "4") (pinfunction "4_4") (pintype "passive"))
      (node (ref "J9") (pin "4") (pinfunction "4_4") (pintype "passive"))
      (node (ref "RN6") (pin "6") (pinfunction "2_6") (pintype "passive"))
    )
    (net (code "31") (name "D12_CIPO") (class "Default")
      (node (ref "IC4") (pin "33") (pinfunction "MISO_33") (pintype "bidirectional"))
      (node (ref "IC6") (pin "2") (pinfunction "PB6(PCINT14/OC3A/MISO)_2") (pintype "bidirectional"))
      (node (ref "J1") (pin "5") (pinfunction "5_5") (pintype "passive"))
      (node (ref "J10") (pin "7") (pinfunction "DO_7") (pintype "bidirectional"))
      (node (ref "J9") (pin "1") (pinfunction "1_1") (pintype "passive"))
    )
    (net (code "32") (name "D13_SCK") (class "Default")
      (node (ref "IC4") (pin "30") (pinfunction "SCLK_30") (pintype "bidirectional"))
      (node (ref "IC6") (pin "3") (pinfunction "PB7(PCINT15/OC3B/SCK)_3") (pintype "bidirectional"))
      (node (ref "J1") (pin "6") (pinfunction "6_6") (pintype "passive"))
      (node (ref "J9") (pin "3") (pinfunction "3_3") (pintype "passive"))
      (node (ref "Q2") (pin "1") (pinfunction "G_1") (pintype "passive"))
      (node (ref "RN6") (pin "7") (pinfunction "2_7") (pintype "passive"))
    )
    (net (code "33") (name "DTR") (class "Default")
      (node (ref "IC2") (pin "23") (pinfunction "DTR_23") (pintype "output"))
      (node (ref "SJ1") (pin "1") (pinfunction "1_1") (pintype "passive"))
    )
    (net (code "34") (name "FDXLED") (class "Default")
      (node (ref "IC4") (pin "19") (pinfunction "~{DPX}_19") (pintype "bidirectional"))
      (node (ref "RN1") (pin "4") (pinfunction "1_4") (pintype "passive"))
      (node (ref "RN2") (pin "8") (pinfunction "2_8") (pintype "passive"))
    )
    (net (code "35") (name "GND") (class "Default")
      (node (ref "C1") (pin "C") (pinfunction "-_C") (pintype "passive"))
      (node (ref "C10") (pin "2") (pinfunction "2_2") (pintype "passive"))
      (node (ref "C11") (pin "2") (pinfunction "2_2") (pintype "passive"))
      (node (ref "C12") (pin "2") (pinfunction "2_2") (pintype "passive"))
      (node (ref "C14") (pin "2") (pinfunction "2_2") (pintype "passive"))
      (node (ref "C15") (pin "2") (pinfunction "2_2") (pintype "passive"))
      (node (ref "C16") (pin "2") (pinfunction "2_2") (pintype "passive"))
      (node (ref "C17") (pin "2") (pinfunction "2_2") (pintype "passive"))
      (node (ref "C18") (pin "2") (pinfunction "2_2") (pintype "passive"))
      (node (ref "C19") (pin "2") (pinfunction "2_2") (pintype "passive"))
      (node (ref "C2") (pin "C") (pinfunction "-_C") (pintype "passive"))
      (node (ref "C20") (pin "2") (pinfunction "2_2") (pintype "passive"))
      (node (ref "C21") (pin "2") (pinfunction "2_2") (pintype "passive"))
      (node (ref "C22") (pin "2") (pinfunction "2_2") (pintype "passive"))
      (node (ref "C23") (pin "2") (pinfunction "2_2") (pintype "passive"))
      (node (ref "C24") (pin "2") (pinfunction "2_2") (pintype "passive"))
      (node (ref "C25") (pin "2") (pinfunction "2_2") (pintype "passive"))
      (node (ref "C26") (pin "1") (pinfunction "1_1") (pintype "passive"))
      (node (ref "C27") (pin "1") (pinfunction "1_1") (pintype "passive"))
      (node (ref "C3") (pin "C") (pinfunction "-_C") (pintype "passive"))
      (node (ref "C4") (pin "C") (pinfunction "-_C") (pintype "passive"))
      (node (ref "C5") (pin "-") (pinfunction "-_-") (pintype "passive"))
      (node (ref "C6") (pin "-") (pinfunction "-_-") (pintype "passive"))
      (node (ref "C7") (pin "2") (pinfunction "2_2") (pintype "passive"))
      (node (ref "C8") (pin "2") (pinfunction "2_2") (pintype "passive"))
      (node (ref "C9") (pin "2") (pinfunction "2_2") (pintype "passive"))
      (node (ref "IC2") (pin "2") (pinfunction "GND_2") (pintype "power_in"))
      (node (ref "IC2") (pin "TGND") (pinfunction "GND_PAD_TGND") (pintype "power_in"))
      (node (ref "IC3") (pin "4") (pinfunction "V-_4") (pintype "power_in"))
      (node (ref "IC4") (pin "1") (pinfunction "GNDA_1") (pintype "bidirectional"))
      (node (ref "IC4") (pin "10") (pinfunction "GND_10") (pintype "bidirectional"))
      (node (ref "IC4") (pin "16") (pinfunction "GNDA_16") (pintype "bidirectional"))
      (node (ref "IC4") (pin "23") (pinfunction "GND_23") (pintype "bidirectional"))
      (node (ref "IC4") (pin "25") (pinfunction "MOD0_25") (pintype "bidirectional"))
      (node (ref "IC4") (pin "26") (pinfunction "MOD1_26") (pintype "bidirectional"))
      (node (ref "IC4") (pin "27") (pinfunction "MOD2_27") (pintype "bidirectional"))
      (node (ref "IC4") (pin "28") (pinfunction "MOD3_28") (pintype "bidirectional"))
      (node (ref "IC4") (pin "46") (pinfunction "GND_46") (pintype "bidirectional"))
      (node (ref "IC4") (pin "7") (pinfunction "GNDA_7") (pintype "bidirectional"))
      (node (ref "IC5") (pin "2") (pinfunction "GND_2") (pintype "power_in"))
      (node (ref "IC5") (pin "4") (pinfunction "A1_4") (pintype "input"))
      (node (ref "IC5") (pin "5") (pinfunction "A0_5") (pintype "input"))
      (node (ref "IC6") (pin "18") (pinfunction "GND_18") (pintype "bidirectional"))
      (node (ref "IC6") (pin "38") (pinfunction "GND_38") (pintype "bidirectional"))
      (node (ref "IC6") (pin "39") (pinfunction "GND_39") (pintype "bidirectional"))
      (node (ref "IC6") (pin "6") (pinfunction "GND_6") (pintype "bidirectional"))
      (node (ref "J1") (pin "7") (pinfunction "7_7") (pintype "passive"))
      (node (ref "J10") (pin "6") (pinfunction "GND_6") (pintype "bidirectional"))
      (node (ref "J10") (pin "CD2") (pinfunction "CD2_CD2") (pintype "bidirectional"))
      (node (ref "J10") (pin "GND1") (pinfunction "SHIELD1_GND1") (pintype "bidirectional"))
      (node (ref "J10") (pin "GND2") (pinfunction "SHIELD2_GND2") (pintype "bidirectional"))
      (node (ref "J11") (pin "GND1") (pinfunction "GND1_GND1") (pintype "bidirectional"))
      (node (ref "J11") (pin "GND2") (pinfunction "GND2_GND2") (pintype "bidirectional"))
      (node (ref "J2") (pin "6") (pinfunction "6_6") (pintype "passive"))
      (node (ref "J2") (pin "7") (pinfunction "7_7") (pintype "passive"))
      (node (ref "J5") (pin "GND") (pinfunction "GND_GND") (pintype "bidirectional"))
      (node (ref "J5") (pin "GNDBREAK") (pinfunction "GNDBREAK_GNDBREAK") (pintype "bidirectional"))
      (node (ref "J6") (pin "A12B1") (pinfunction "GND_A12B1") (pintype "power_in"))
      (node (ref "J6") (pin "A1B12") (pinfunction "GND_A1B12") (pintype "power_in"))
      (node (ref "J6") (pin "FIX1") (pinfunction "GND_FIX1") (pintype "power_in"))
      (node (ref "J6") (pin "FIX2") (pinfunction "GND_FIX2") (pintype "power_in"))
      (node (ref "J6") (pin "FIX3") (pinfunction "GND_FIX3") (pintype "power_in"))
      (node (ref "J6") (pin "FIX4") (pinfunction "GND_FIX4") (pintype "power_in"))
      (node (ref "J8") (pin "1") (pinfunction "GND[1]_1") (pintype "passive"))
      (node (ref "J9") (pin "6") (pinfunction "6_6") (pintype "passive"))
      (node (ref "Q2") (pin "2") (pinfunction "S_2") (pintype "passive"))
      (node (ref "R1") (pin "1") (pinfunction "1_1") (pintype "passive"))
      (node (ref "R2") (pin "1") (pinfunction "1_1") (pintype "passive"))
      (node (ref "R5") (pin "2") (pinfunction "2_2") (pintype "passive"))
      (node (ref "R8") (pin "1") (pinfunction "1_1") (pintype "passive"))
      (node (ref "REG1") (pin "1") (pinfunction "ADJ_1") (pintype "input"))
      (node (ref "REG2") (pin "1") (pinfunction "GND_1") (pintype "input"))
      (node (ref "REG3") (pin "1") (pinfunction "GND_1") (pintype "input"))
      (node (ref "RN4") (pin "4") (pinfunction "1_4") (pintype "passive"))
      (node (ref "RN6") (pin "1") (pinfunction "1_1") (pintype "passive"))
      (node (ref "RN7") (pin "1") (pinfunction "1_1") (pintype "passive"))
      (node (ref "RN7") (pin "2") (pinfunction "1_2") (pintype "passive"))
      (node (ref "RN7") (pin "3") (pinfunction "1_3") (pintype "passive"))
      (node (ref "S1") (pin "1") (pinfunction "1_1") (pintype "passive"))
      (node (ref "S1") (pin "2") (pinfunction "2_2") (pintype "passive"))
      (node (ref "XTL1") (pin "2") (pinfunction "GND_2") (pintype "bidirectional"))
      (node (ref "XTL1") (pin "4") (pinfunction "GND_4") (pintype "bidirectional"))
      (node (ref "XTL2") (pin "2") (pinfunction "GND_2") (pintype "bidirectional"))
      (node (ref "XTL2") (pin "4") (pinfunction "GND_4") (pintype "bidirectional"))
      (node (ref "Z1") (pin "2") (pinfunction "2_2") (pintype "passive"))
      (node (ref "Z2") (pin "2") (pinfunction "2_2") (pintype "passive"))
    )
    (net (code "36") (name "LINKLED") (class "Default")
      (node (ref "IC4") (pin "17") (pinfunction "~{LINK}_17") (pintype "bidirectional"))
      (node (ref "RN2") (pin "4") (pinfunction "1_4") (pintype "passive"))
      (node (ref "RN2") (pin "7") (pinfunction "2_7") (pintype "passive"))
    )
    (net (code "37") (name "Net-(C13-Pad1)") (class "Default")
      (node (ref "C13") (pin "1") (pinfunction "1_1") (pintype "passive"))
      (node (ref "SJ1") (pin "2") (pinfunction "2_2") (pintype "passive"))
    )
    (net (code "38") (name "Net-(CD-Pad1)") (class "Default")
      (node (ref "CD") (pin "1") (pinfunction "1_1") (pintype "passive"))
      (node (ref "J10") (pin "CD1") (pinfunction "CD1_CD1") (pintype "bidirectional"))
    )
    (net (code "39") (name "Net-(D1-PadA)") (class "Default")
      (node (ref "D1") (pin "A") (pinfunction "A_A") (pintype "passive"))
      (node (ref "J5") (pin "PWR") (pinfunction "PWR_PWR") (pintype "bidirectional"))
    )
    (net (code "40") (name "Net-(F1-Pad1)") (class "Default")
      (node (ref "F1") (pin "1") (pinfunction "1_1") (pintype "passive"))
      (node (ref "J6") (pin "A4B9") (pinfunction "VBUS_A4B9") (pintype "power_in"))
      (node (ref "J6") (pin "A9B4") (pinfunction "VBUS_A9B4") (pintype "power_in"))
    )
    (net (code "41") (name "Net-(IC2-RXD)") (class "Default")
      (node (ref "IC2") (pin "20") (pinfunction "RXD_20") (pintype "input"))
      (node (ref "RN3") (pin "6") (pinfunction "2_6") (pintype "passive"))
    )
    (net (code "42") (name "Net-(IC2-TXD)") (class "Default")
      (node (ref "IC2") (pin "21") (pinfunction "TXD_21") (pintype "output"))
      (node (ref "RN3") (pin "5") (pinfunction "2_5") (pintype "passive"))
    )
    (net (code "43") (name "Net-(IC2-VBUS)") (class "Default")
      (node (ref "IC2") (pin "8") (pinfunction "VBUS_8") (pintype "bidirectional"))
      (node (ref "R7") (pin "1") (pinfunction "1_1") (pintype "passive"))
      (node (ref "R8") (pin "2") (pinfunction "2_2") (pintype "passive"))
    )
    (net (code "44") (name "Net-(IC3A-+IN)") (class "Default")
      (node (ref "IC3") (pin "3") (pinfunction "+IN_3") (pintype "input"))
      (node (ref "RN4") (pin "5") (pinfunction "2_5") (pintype "passive"))
      (node (ref "RN4") (pin "6") (pinfunction "2_6") (pintype "passive"))
    )
    (net (code "45") (name "Net-(IC3A-OUT)") (class "Default")
      (node (ref "IC3") (pin "1") (pinfunction "OUT_1") (pintype "output"))
      (node (ref "IC3") (pin "5") (pinfunction "+IN_5") (pintype "input"))
    )
    (net (code "46") (name "Net-(IC3B--IN)") (class "Default")
      (node (ref "IC3") (pin "6") (pinfunction "-IN_6") (pintype "input"))
      (node (ref "IC3") (pin "7") (pinfunction "OUT_7") (pintype "output"))
      (node (ref "Q1") (pin "1") (pinfunction "G_1") (pintype "passive"))
    )
    (net (code "47") (name "Net-(IC4-RSET_BG)") (class "Default")
      (node (ref "IC4") (pin "9") (pinfunction "RSET_BG_9") (pintype "bidirectional"))
      (node (ref "R4") (pin "1") (pinfunction "1_1") (pintype "passive"))
    )
    (net (code "48") (name "Net-(IC4-XSCI)") (class "Default")
      (node (ref "C25") (pin "1") (pinfunction "1_1") (pintype "passive"))
      (node (ref "IC4") (pin "12") (pinfunction "XSCI_12") (pintype "bidirectional"))
      (node (ref "XTL1") (pin "1") (pinfunction "1_1") (pintype "passive"))
    )
    (net (code "49") (name "Net-(IC4-XSCO)") (class "Default")
      (node (ref "C24") (pin "1") (pinfunction "1_1") (pintype "passive"))
      (node (ref "IC4") (pin "11") (pinfunction "XSCO_11") (pintype "bidirectional"))
      (node (ref "XTL1") (pin "3") (pinfunction "2_3") (pintype "passive"))
    )
    (net (code "50") (name "Net-(IC4-~{INT})") (class "Default")
      (node (ref "IC4") (pin "47") (pinfunction "~{INT}_47") (pintype "bidirectional"))
      (node (ref "J7") (pin "1") (pinfunction "1_1") (pintype "passive"))
      (node (ref "R3") (pin "2") (pinfunction "2_2") (pintype "passive"))
    )
    (net (code "51") (name "Net-(IC5-SCL)") (class "Default")
      (node (ref "IC5") (pin "1") (pinfunction "SCL_1") (pintype "bidirectional"))
      (node (ref "R10") (pin "2") (pinfunction "2_2") (pintype "passive"))
      (node (ref "SJ4") (pin "2") (pinfunction "2_2") (pintype "passive"))
    )
    (net (code "52") (name "Net-(IC5-SDA)") (class "Default")
      (node (ref "IC5") (pin "3") (pinfunction "SDA_3") (pintype "bidirectional"))
      (node (ref "R9") (pin "2") (pinfunction "2_2") (pintype "passive"))
      (node (ref "SJ3") (pin "2") (pinfunction "2_2") (pintype "passive"))
    )
    (net (code "53") (name "Net-(IC6-XTAL1)") (class "Default")
      (node (ref "C26") (pin "2") (pinfunction "2_2") (pintype "passive"))
      (node (ref "IC6") (pin "8") (pinfunction "XTAL1_8") (pintype "bidirectional"))
      (node (ref "XTL2") (pin "1") (pinfunction "1_1") (pintype "passive"))
    )
    (net (code "54") (name "Net-(IC6-XTAL2)") (class "Default")
      (node (ref "C27") (pin "2") (pinfunction "2_2") (pintype "passive"))
      (node (ref "IC6") (pin "7") (pinfunction "XTAL2_7") (pintype "bidirectional"))
      (node (ref "XTL2") (pin "3") (pinfunction "2_3") (pintype "passive"))
    )
    (net (code "55") (name "Net-(J6-CC1)") (class "Default")
      (node (ref "J6") (pin "A5") (pinfunction "CC1_A5") (pintype "bidirectional"))
      (node (ref "R2") (pin "2") (pinfunction "2_2") (pintype "passive"))
    )
    (net (code "56") (name "Net-(J6-CC2)") (class "Default")
      (node (ref "J6") (pin "B5") (pinfunction "CC2_B5") (pintype "bidirectional"))
      (node (ref "R1") (pin "2") (pinfunction "2_2") (pintype "passive"))
    )
    (net (code "57") (name "Net-(J10-CS)") (class "Default")
      (node (ref "J10") (pin "2") (pinfunction "CS_2") (pintype "bidirectional"))
      (node (ref "RN6") (pin "4") (pinfunction "1_4") (pintype "passive"))
      (node (ref "RN7") (pin "8") (pinfunction "2_8") (pintype "passive"))
    )
    (net (code "58") (name "Net-(J10-DI)") (class "Default")
      (node (ref "J10") (pin "3") (pinfunction "DI_3") (pintype "bidirectional"))
      (node (ref "RN6") (pin "3") (pinfunction "1_3") (pintype "passive"))
      (node (ref "RN7") (pin "6") (pinfunction "2_6") (pintype "passive"))
    )
    (net (code "59") (name "Net-(J10-SCK)") (class "Default")
      (node (ref "J10") (pin "5") (pinfunction "SCK_5") (pintype "bidirectional"))
      (node (ref "RN6") (pin "2") (pinfunction "1_2") (pintype "passive"))
      (node (ref "RN7") (pin "7") (pinfunction "2_7") (pintype "passive"))
    )
    (net (code "60") (name "Net-(J11-G-)") (class "Default")
      (node (ref "J11") (pin "P$14") (pinfunction "G-_P$14") (pintype "bidirectional"))
      (node (ref "RN2") (pin "1") (pinfunction "1_1") (pintype "passive"))
    )
    (net (code "61") (name "Net-(J11-V+)") (class "Default")
      (node (ref "J11") (pin "P$9") (pinfunction "V+_P$9") (pintype "bidirectional"))
      (node (ref "J8") (pin "3") (pinfunction "V+[3]_3") (pintype "passive"))
    )
    (net (code "62") (name "Net-(J11-V-)") (class "Default")
      (node (ref "J11") (pin "P$10") (pinfunction "V-_P$10") (pintype "bidirectional"))
      (node (ref "J8") (pin "2") (pinfunction "V-[2]_2") (pintype "passive"))
    )
    (net (code "63") (name "Net-(J11-Y-)") (class "Default")
      (node (ref "J11") (pin "P$12") (pinfunction "Y-_P$12") (pintype "bidirectional"))
      (node (ref "RN2") (pin "2") (pinfunction "1_2") (pintype "passive"))
    )
    (net (code "64") (name "Net-(LED4-PadC)") (class "Default")
      (node (ref "LED4") (pin "C") (pinfunction "C_C") (pintype "passive"))
      (node (ref "RN3") (pin "1") (pinfunction "1_1") (pintype "passive"))
    )
    (net (code "65") (name "Net-(LED9-PadC)") (class "Default")
      (node (ref "LED9") (pin "C") (pinfunction "C_C") (pintype "passive"))
      (node (ref "R6") (pin "2") (pinfunction "2_2") (pintype "passive"))
    )
    (net (code "66") (name "Net-(Q2-D)") (class "Default")
      (node (ref "Q2") (pin "3") (pinfunction "D_3") (pintype "passive"))
      (node (ref "R6") (pin "1") (pinfunction "1_1") (pintype "passive"))
    )
    (net (code "67") (name "Net-(R4-Pad2)") (class "Default")
      (node (ref "R4") (pin "2") (pinfunction "2_2") (pintype "passive"))
      (node (ref "R5") (pin "1") (pinfunction "1_1") (pintype "passive"))
    )
    (net (code "68") (name "Net-(RN1A-2)") (class "Default")
      (node (ref "LED3") (pin "C") (pinfunction "C_C") (pintype "passive"))
      (node (ref "RN1") (pin "8") (pinfunction "2_8") (pintype "passive"))
    )
    (net (code "69") (name "Net-(RN1B-2)") (class "Default")
      (node (ref "LED2") (pin "C") (pinfunction "C_C") (pintype "passive"))
      (node (ref "RN1") (pin "7") (pinfunction "2_7") (pintype "passive"))
    )
    (net (code "70") (name "Net-(RN1D-2)") (class "Default")
      (node (ref "LED6") (pin "C") (pinfunction "C_C") (pintype "passive"))
      (node (ref "RN1") (pin "5") (pinfunction "2_5") (pintype "passive"))
    )
    (net (code "71") (name "Net-(RN2C-2)") (class "Default")
      (node (ref "LED7") (pin "C") (pinfunction "C_C") (pintype "passive"))
      (node (ref "RN2") (pin "6") (pinfunction "2_6") (pintype "passive"))
    )
    (net (code "72") (name "Net-(RN2D-2)") (class "Default")
      (node (ref "LED8") (pin "C") (pinfunction "C_C") (pintype "passive"))
      (node (ref "RN2") (pin "5") (pinfunction "2_5") (pintype "passive"))
    )
    (net (code "73") (name "Net-(RN3B-1)") (class "Default")
      (node (ref "LED5") (pin "C") (pinfunction "C_C") (pintype "passive"))
      (node (ref "RN3") (pin "2") (pinfunction "1_2") (pintype "passive"))
    )
    (net (code "74") (name "Net-(RN5A-2)") (class "Default")
      (node (ref "C17") (pin "1") (pinfunction "1_1") (pintype "passive"))
      (node (ref "RN5") (pin "7") (pinfunction "2_7") (pintype "passive"))
      (node (ref "RN5") (pin "8") (pinfunction "2_8") (pintype "passive"))
    )
    (net (code "75") (name "Net-(RN5C-2)") (class "Default")
      (node (ref "C18") (pin "1") (pinfunction "1_1") (pintype "passive"))
      (node (ref "RN5") (pin "5") (pinfunction "2_5") (pintype "passive"))
      (node (ref "RN5") (pin "6") (pinfunction "2_6") (pintype "passive"))
    )
    (net (code "76") (name "Net-(RN6A-2)") (class "Default")
      (node (ref "LED1") (pin "C") (pinfunction "C_C") (pintype "passive"))
      (node (ref "RN6") (pin "8") (pinfunction "2_8") (pintype "passive"))
    )
    (net (code "77") (name "Net-(RN6D-2)") (class "Default")
      (node (ref "RN6") (pin "5") (pinfunction "2_5") (pintype "passive"))
      (node (ref "SJ5") (pin "1") (pinfunction "1_1") (pintype "passive"))
    )
    (net (code "78") (name "RESET") (class "Default")
      (node (ref "C13") (pin "2") (pinfunction "2_2") (pintype "passive"))
      (node (ref "IC4") (pin "48") (pinfunction "~{RESET}_48") (pintype "bidirectional"))
      (node (ref "IC6") (pin "4") (pinfunction "~{RESET}_4") (pintype "bidirectional"))
      (node (ref "J2") (pin "3") (pinfunction "3_3") (pintype "passive"))
      (node (ref "J9") (pin "5") (pinfunction "5_5") (pintype "passive"))
      (node (ref "RN4") (pin "2") (pinfunction "1_2") (pintype "passive"))
      (node (ref "S1") (pin "3") (pinfunction "3_3") (pintype "passive"))
      (node (ref "S1") (pin "4") (pinfunction "4_4") (pintype "passive"))
    )
    (net (code "79") (name "RXIN") (class "Default")
      (node (ref "IC4") (pin "5") (pinfunction "RXIN_5") (pintype "bidirectional"))
      (node (ref "J11") (pin "P$2") (pinfunction "RX-_P$2") (pintype "bidirectional"))
      (node (ref "RN5") (pin "2") (pinfunction "1_2") (pintype "passive"))
    )
    (net (code "80") (name "RXIP") (class "Default")
      (node (ref "IC4") (pin "6") (pinfunction "RXIP_6") (pintype "bidirectional"))
      (node (ref "J11") (pin "P$1") (pinfunction "RX+_P$1") (pintype "bidirectional"))
      (node (ref "RN5") (pin "1") (pinfunction "1_1") (pintype "passive"))
    )
    (net (code "81") (name "RX_LED") (class "Default")
      (node (ref "IC2") (pin "13") (pinfunction "GPIO_1_13") (pintype "bidirectional"))
      (node (ref "RN3") (pin "7") (pinfunction "2_7") (pintype "passive"))
    )
    (net (code "82") (name "SCL") (class "Default")
      (node (ref "IC6") (pin "19") (pinfunction "PC0(SCL/PCINT16)_19") (pintype "bidirectional"))
      (node (ref "J1") (pin "10") (pinfunction "10_10") (pintype "passive"))
      (node (ref "SJ4") (pin "1") (pinfunction "1_1") (pintype "passive"))
    )
    (net (code "83") (name "SDA") (class "Default")
      (node (ref "IC6") (pin "20") (pinfunction "PC1(SDA/PCINT17)_20") (pintype "bidirectional"))
      (node (ref "J1") (pin "9") (pinfunction "9_9") (pintype "passive"))
      (node (ref "SJ3") (pin "1") (pinfunction "1_1") (pintype "passive"))
    )
    (net (code "84") (name "SPDLED") (class "Default")
      (node (ref "IC4") (pin "18") (pinfunction "~{SPD}_18") (pintype "bidirectional"))
      (node (ref "RN2") (pin "3") (pinfunction "1_3") (pintype "passive"))
    )
    (net (code "85") (name "TXON") (class "Default")
      (node (ref "IC4") (pin "2") (pinfunction "TXON_2") (pintype "bidirectional"))
      (node (ref "J11") (pin "P$6") (pinfunction "TX-_P$6") (pintype "bidirectional"))
      (node (ref "RN5") (pin "4") (pinfunction "1_4") (pintype "passive"))
    )
    (net (code "86") (name "TXOP") (class "Default")
      (node (ref "IC4") (pin "3") (pinfunction "TXOP_3") (pintype "bidirectional"))
      (node (ref "J11") (pin "P$5") (pinfunction "TX+_P$5") (pintype "bidirectional"))
      (node (ref "RN5") (pin "3") (pinfunction "1_3") (pintype "passive"))
    )
    (net (code "87") (name "TX_LED") (class "Default")
      (node (ref "IC2") (pin "14") (pinfunction "GPIO_0_14") (pintype "bidirectional"))
      (node (ref "RN3") (pin "8") (pinfunction "2_8") (pintype "passive"))
    )
    (net (code "88") (name "USBVCC") (class "Default")
      (node (ref "F1") (pin "2") (pinfunction "2_2") (pintype "passive"))
      (node (ref "Q1") (pin "3") (pinfunction "D_3") (pintype "passive"))
    )
    (net (code "89") (name "VIN") (class "Default")
      (node (ref "C5") (pin "+") (pinfunction "+_+") (pintype "passive"))
      (node (ref "D1") (pin "C") (pinfunction "C_C") (pintype "passive"))
      (node (ref "J2") (pin "8") (pinfunction "8_8") (pintype "passive"))
      (node (ref "J8") (pin "4") (pinfunction "VIN[4]_4") (pintype "passive"))
      (node (ref "REG1") (pin "3") (pinfunction "VI_3") (pintype "input"))
      (node (ref "RN4") (pin "3") (pinfunction "1_3") (pintype "passive"))
    )
    (net (code "90") (name "unconnected-(IC2-CTS-Pad18)") (class "Default")
      (node (ref "IC2") (pin "18") (pinfunction "CTS_18") (pintype "input"))
    )
    (net (code "91") (name "unconnected-(IC2-DCD-Pad24)") (class "Default")
      (node (ref "IC2") (pin "24") (pinfunction "DCD_24") (pintype "input"))
    )
    (net (code "92") (name "unconnected-(IC2-DSR-Pad22)") (class "Default")
      (node (ref "IC2") (pin "22") (pinfunction "DSR_22") (pintype "input"))
    )
    (net (code "93") (name "unconnected-(IC2-GPIO_2-Pad12)") (class "Default")
      (node (ref "IC2") (pin "12") (pinfunction "GPIO_2_12") (pintype "bidirectional"))
    )
    (net (code "94") (name "unconnected-(IC2-GPIO_3-Pad11)") (class "Default")
      (node (ref "IC2") (pin "11") (pinfunction "GPIO_3_11") (pintype "bidirectional"))
    )
    (net (code "95") (name "unconnected-(IC2-NC-Pad10)") (class "Default")
      (node (ref "IC2") (pin "10") (pinfunction "NC_10") (pintype "input"))
    )
    (net (code "96") (name "unconnected-(IC2-RI-Pad1)") (class "Default")
      (node (ref "IC2") (pin "1") (pinfunction "RI_1") (pintype "input"))
    )
    (net (code "97") (name "unconnected-(IC2-RTS-Pad19)") (class "Default")
      (node (ref "IC2") (pin "19") (pinfunction "RTS_19") (pintype "output"))
    )
    (net (code "98") (name "unconnected-(IC2-SUSPEND-Pad17)") (class "Default")
      (node (ref "IC2") (pin "17") (pinfunction "SUSPEND_17") (pintype "output"))
    )
    (net (code "99") (name "unconnected-(IC2-VPP-Pad16)") (class "Default")
      (node (ref "IC2") (pin "16") (pinfunction "VPP_16") (pintype "bidirectional"))
    )
    (net (code "100") (name "unconnected-(IC2-~{RST}-Pad9)") (class "Default")
      (node (ref "IC2") (pin "9") (pinfunction "~{RST}_9") (pintype "bidirectional"))
    )
    (net (code "101") (name "unconnected-(IC2-~{SUSPEND}-Pad15)") (class "Default")
      (node (ref "IC2") (pin "15") (pinfunction "~{SUSPEND}_15") (pintype "output"))
    )
    (net (code "102") (name "unconnected-(IC4-DAT0-Pad37)") (class "Default")
      (node (ref "IC4") (pin "37") (pinfunction "DAT0_37") (pintype "bidirectional"))
    )
    (net (code "103") (name "unconnected-(IC4-DAT1-Pad38)") (class "Default")
      (node (ref "IC4") (pin "38") (pinfunction "DAT1_38") (pintype "bidirectional"))
    )
    (net (code "104") (name "unconnected-(IC4-DAT2-Pad39)") (class "Default")
      (node (ref "IC4") (pin "39") (pinfunction "DAT2_39") (pintype "bidirectional"))
    )
    (net (code "105") (name "unconnected-(IC4-DAT3-Pad40)") (class "Default")
      (node (ref "IC4") (pin "40") (pinfunction "DAT3_40") (pintype "bidirectional"))
    )
    (net (code "106") (name "unconnected-(IC4-DAT4-Pad41)") (class "Default")
      (node (ref "IC4") (pin "41") (pinfunction "DAT4_41") (pintype "bidirectional"))
    )
    (net (code "107") (name "unconnected-(IC4-DAT5-Pad42)") (class "Default")
      (node (ref "IC4") (pin "42") (pinfunction "DAT5_42") (pintype "bidirectional"))
    )
    (net (code "108") (name "unconnected-(IC4-DAT6-Pad43)") (class "Default")
      (node (ref "IC4") (pin "43") (pinfunction "DAT6_43") (pintype "bidirectional"))
    )
    (net (code "109") (name "unconnected-(IC4-DAT7-Pad44)") (class "Default")
      (node (ref "IC4") (pin "44") (pinfunction "DAT7_44") (pintype "bidirectional"))
    )
    (net (code "110") (name "unconnected-(IC4-~{RD}-Pad34)") (class "Default")
      (node (ref "IC4") (pin "34") (pinfunction "~{RD}_34") (pintype "bidirectional"))
    )
    (net (code "111") (name "unconnected-(IC4-~{WR}-Pad35)") (class "Default")
      (node (ref "IC4") (pin "35") (pinfunction "~{WR}_35") (pintype "bidirectional"))
    )
    (net (code "112") (name "unconnected-(IC6-PA0(ADC0{slash}PCINT0)-Pad37)") (class "Default")
      (node (ref "IC6") (pin "37") (pinfunction "PA0(ADC0/PCINT0)_37") (pintype "bidirectional"))
    )
    (net (code "113") (name "unconnected-(IC6-PA1(ADC1{slash}PCINT1)-Pad36)") (class "Default")
      (node (ref "IC6") (pin "36") (pinfunction "PA1(ADC1/PCINT1)_36") (pintype "bidirectional"))
    )
    (net (code "114") (name "unconnected-(IC6-PC2(TCK{slash}PCINT18)-Pad21)") (class "Default")
      (node (ref "IC6") (pin "21") (pinfunction "PC2(TCK/PCINT18)_21") (pintype "bidirectional"))
    )
    (net (code "115") (name "unconnected-(IC6-PC3(TMS{slash}PCINT19)-Pad22)") (class "Default")
      (node (ref "IC6") (pin "22") (pinfunction "PC3(TMS/PCINT19)_22") (pintype "bidirectional"))
    )
    (net (code "116") (name "unconnected-(IC6-PC4(TDO{slash}PCINT20)-Pad23)") (class "Default")
      (node (ref "IC6") (pin "23") (pinfunction "PC4(TDO/PCINT20)_23") (pintype "bidirectional"))
    )
    (net (code "117") (name "unconnected-(IC6-PC5(TDI{slash}PCINT21)-Pad24)") (class "Default")
      (node (ref "IC6") (pin "24") (pinfunction "PC5(TDI/PCINT21)_24") (pintype "bidirectional"))
    )
    (net (code "118") (name "unconnected-(IC6-PC6(TOSC1{slash}PCINT22)-Pad25)") (class "Default")
      (node (ref "IC6") (pin "25") (pinfunction "PC6(TOSC1/PCINT22)_25") (pintype "bidirectional"))
    )
    (net (code "119") (name "unconnected-(IC6-PC7(TOSC2{slash}PCINT23)-Pad26)") (class "Default")
      (node (ref "IC6") (pin "26") (pinfunction "PC7(TOSC2/PCINT23)_26") (pintype "bidirectional"))
    )
    (net (code "120") (name "unconnected-(IC6-PD4(PCINT28{slash}XCK1{slash}OC1B)-Pad13)") (class "Default")
      (node (ref "IC6") (pin "13") (pinfunction "PD4(PCINT28/XCK1/OC1B)_13") (pintype "bidirectional"))
    )
    (net (code "121") (name "unconnected-(IC6-PD7(OC2A{slash}PCINT31)-Pad16)") (class "Default")
      (node (ref "IC6") (pin "16") (pinfunction "PD7(OC2A/PCINT31)_16") (pintype "bidirectional"))
    )
    (net (code "122") (name "unconnected-(J2-Pad1)") (class "Default")
      (node (ref "J2") (pin "1") (pinfunction "1_1") (pintype "passive"))
    )
    (net (code "123") (name "unconnected-(J6-SBU1-PadA8)") (class "Default")
      (node (ref "J6") (pin "A8") (pinfunction "SBU1_A8") (pintype "bidirectional"))
    )
    (net (code "124") (name "unconnected-(J6-SBU2-PadB8)") (class "Default")
      (node (ref "J6") (pin "B8") (pinfunction "SBU2_B8") (pintype "bidirectional"))
    )
    (net (code "125") (name "unconnected-(J8-PadMNT1)") (class "Default")
      (node (ref "J8") (pin "MNT1") (pinfunction "MNT1_MNT1") (pintype "passive"))
    )
    (net (code "126") (name "unconnected-(J8-PadMNT2)") (class "Default")
      (node (ref "J8") (pin "MNT2") (pinfunction "MNT2_MNT2") (pintype "passive"))
    )
    (net (code "127") (name "unconnected-(J10-NC-Pad1)") (class "Default")
      (node (ref "J10") (pin "1") (pinfunction "NC_1") (pintype "bidirectional"))
    )
    (net (code "128") (name "unconnected-(J10-RSV-Pad8)") (class "Default")
      (node (ref "J10") (pin "8") (pinfunction "RSV_8") (pintype "bidirectional"))
    )
    (net (code "129") (name "unconnected-(RN1C-1-Pad3)") (class "Default")
      (node (ref "RN1") (pin "3") (pinfunction "1_3") (pintype "passive"))
    )
    (net (code "130") (name "unconnected-(RN1C-2-Pad6)") (class "Default")
      (node (ref "RN1") (pin "6") (pinfunction "2_6") (pintype "passive"))
    )
    (net (code "131") (name "unconnected-(RN4-Pad1)") (class "Default")
      (node (ref "RN4") (pin "1") (pinfunction "1_1") (pintype "passive"))
    )
    (net (code "132") (name "unconnected-(RN4A-2-Pad8)") (class "Default")
      (node (ref "RN4") (pin "8") (pinfunction "2_8") (pintype "passive"))
    )
    (net (code "133") (name "unconnected-(RN7D-1-Pad4)") (class "Default")
      (node (ref "RN7") (pin "4") (pinfunction "1_4") (pintype "passive"))
    )
    (net (code "134") (name "unconnected-(RN7D-2-Pad5)") (class "Default")
      (node (ref "RN7") (pin "5") (pinfunction "2_5") (pintype "passive"))
    )
  )
)
